# QSPI.net
KiCad netlist of a schematic drawn in Altium Designer
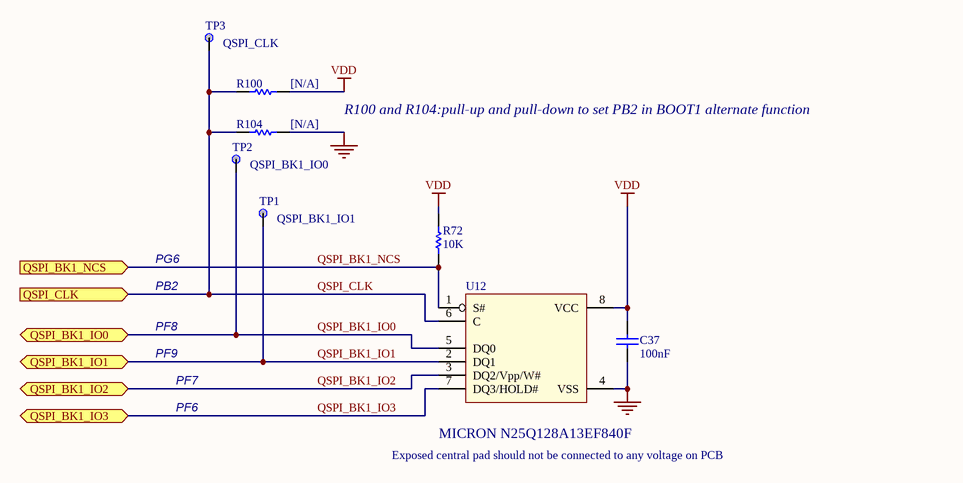
[diagram p0: QSPI.SchDoc]

(export (version "E")
  (design (tool "Eeschema 10.0.6"))
  (components
    (comp (ref "C37")
      (value "100nF")
      (footprint "0402C")
      (description "Capacitor")
      (fields (field (name "PUBLISHER") "Altium Limited"))
      (libsource (lib "Miscellaneous Devices") (part "Cap"))
    )
    (comp (ref "R72")
      (value "10K")
      (footprint "0402R")
      (description "Resistor")
      (libsource (lib "MCD_TOOLS") (part "Res_10K_1%_0402"))
    )
    (comp (ref "R100")
      (value "[N/A]")
      (footprint "0603R")
      (description "Resistor")
      (fields (field (name "PUBLISHER") "Altium Limited"))
      (libsource (lib "Miscellaneous Devices") (part "Res1"))
    )
    (comp (ref "R104")
      (value "[N/A]")
      (footprint "0603R")
      (description "Resistor")
      (fields (field (name "PUBLISHER") "Altium Limited"))
      (libsource (lib "Miscellaneous Devices") (part "Res1"))
    )
    (comp (ref "TP1")
      (value "TP")
      (footprint "TP_C40")
      (fields (field (name "TP NAME") "QSPI_BK1_IO1"))
      (libsource (lib "Almos") (part "TP"))
    )
    (comp (ref "TP2")
      (value "TP")
      (footprint "TP_C40")
      (fields (field (name "TP NAME") "QSPI_BK1_IO0"))
      (libsource (lib "Almos") (part "TP"))
    )
    (comp (ref "TP3")
      (value "TP")
      (footprint "TP_C40")
      (fields (field (name "TP NAME") "QSPI_CLK"))
      (libsource (lib "Almos") (part "TP"))
    )
    (comp (ref "U12")
      (value "MICRON N25Q128A13EF840F")
      (footprint "DFN8_1R27_6X8_TP4R8X5R8")
      (description "128Mb, 3V, Multiple I/O Serial Flash Memory, Quad/Dual")
      (libsource (lib "MCD_TOOLS") (part "N25Q128A13EF840E"))
    )
  )
  (nets
    (net (code "1") (name "/QSPI_BK1_IO0") (class "Default")
      (node (ref "TP2") (pin "1") (pinfunction "1_1") (pintype "passive"))
      (node (ref "U12") (pin "5") (pinfunction "DQ0_5") (pintype "passive"))
    )
    (net (code "2") (name "/QSPI_BK1_IO1") (class "Default")
      (node (ref "TP1") (pin "1") (pinfunction "1_1") (pintype "passive"))
      (node (ref "U12") (pin "2") (pinfunction "DQ1_2") (pintype "passive"))
    )
    (net (code "3") (name "/QSPI_BK1_IO2") (class "Default")
      (node (ref "U12") (pin "3") (pinfunction "DQ2/Vpp/W#_3") (pintype "passive"))
    )
    (net (code "4") (name "/QSPI_BK1_IO3") (class "Default")
      (node (ref "U12") (pin "7") (pinfunction "DQ3/HOLD#_7") (pintype "passive"))
    )
    (net (code "5") (name "/QSPI_BK1_NCS") (class "Default")
      (node (ref "R72") (pin "1") (pinfunction "1_1") (pintype "passive"))
      (node (ref "U12") (pin "1") (pinfunction "S#_1") (pintype "passive"))
    )
    (net (code "6") (name "/QSPI_CLK") (class "Default")
      (node (ref "R100") (pin "2") (pinfunction "2_2") (pintype "passive"))
      (node (ref "R104") (pin "2") (pinfunction "2_2") (pintype "passive"))
      (node (ref "TP3") (pin "1") (pinfunction "1_1") (pintype "passive"))
      (node (ref "U12") (pin "6") (pinfunction "C_6") (pintype "passive"))
    )
    (net (code "7") (name "GND") (class "Default")
      (node (ref "C37") (pin "2") (pinfunction "2_2") (pintype "passive"))
      (node (ref "R104") (pin "1") (pinfunction "1_1") (pintype "passive"))
      (node (ref "U12") (pin "4") (pinfunction "VSS_4") (pintype "passive"))
    )
    (net (code "8") (name "VDD") (class "Default")
      (node (ref "C37") (pin "1") (pinfunction "1_1") (pintype "passive"))
      (node (ref "R100") (pin "1") (pinfunction "1_1") (pintype "passive"))
      (node (ref "R72") (pin "2") (pinfunction "2_2") (pintype "passive"))
      (node (ref "U12") (pin "8") (pinfunction "VCC_8") (pintype "passive"))
    )
  )
)
